# WWV_Radio_V1_11.net
KiCad netlist of a schematic drawn in EAGLE
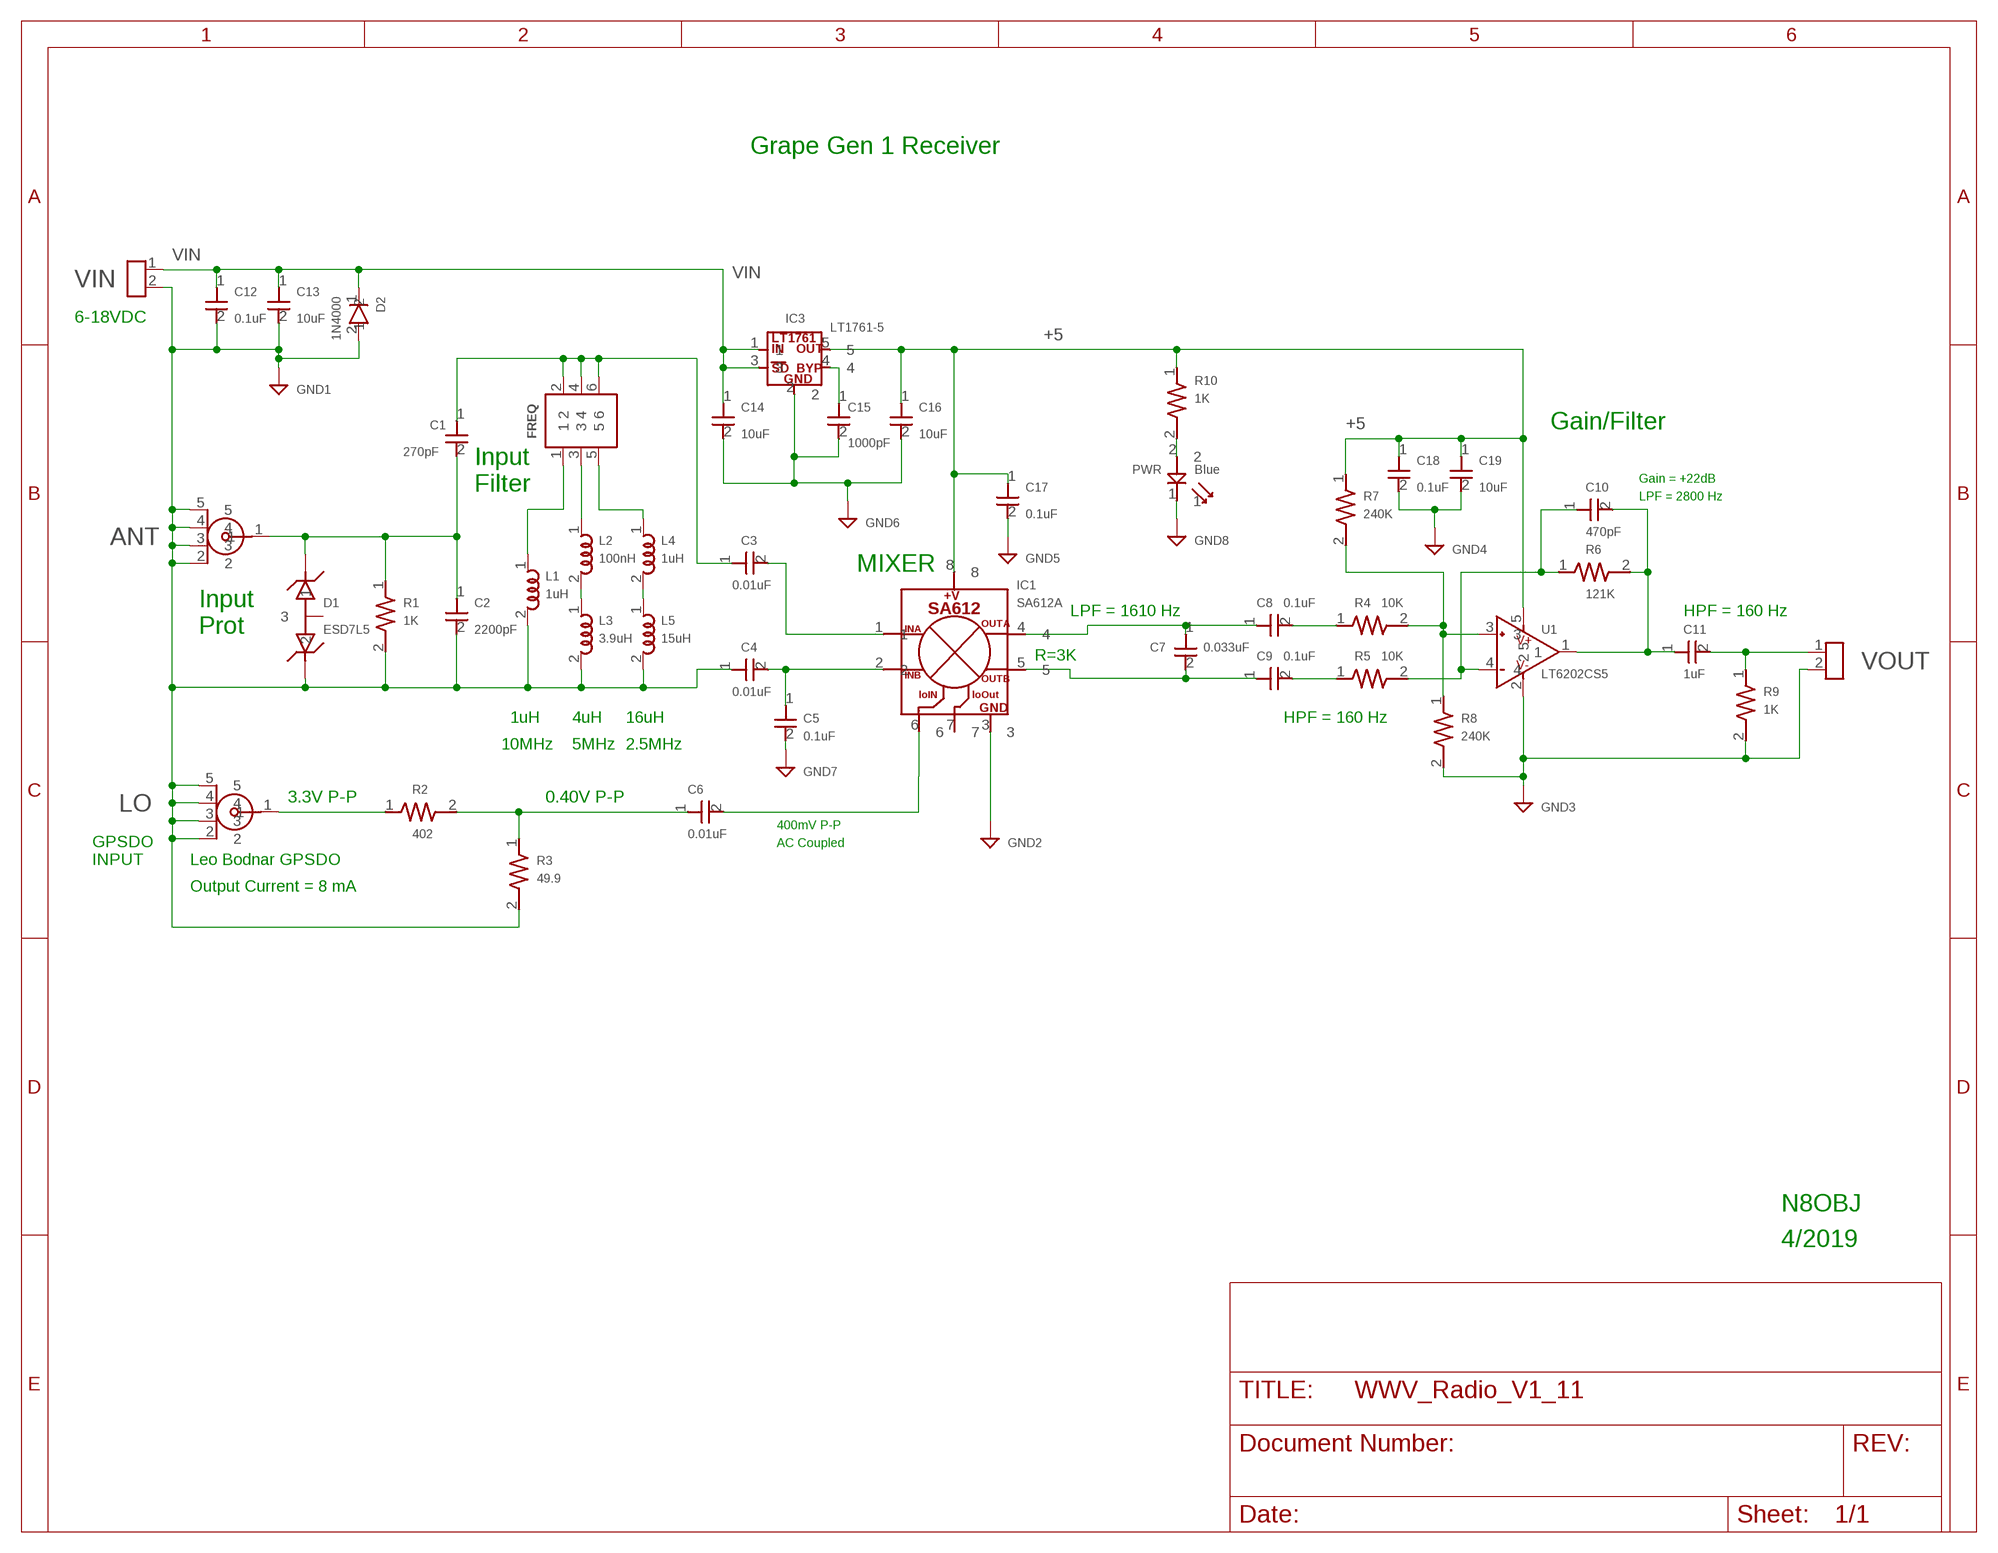
[diagram p0: schematic, sheet 1]

(export (version "E")
  (design (tool "Eeschema 10.0.6"))
  (components
    (comp (ref "ANT")
      (value "SMAEDGEPCB")
      (footprint "eagle-import:SMAEDGEPCB")
      (libsource (lib "eagle-import") (part "SMAEDGEPCB"))
    )
    (comp (ref "C1")
      (value "270pF")
      (footprint "eagle-import:C0805")
      (libsource (lib "eagle-import") (part "C0805"))
    )
    (comp (ref "C2")
      (value "2200pF")
      (footprint "eagle-import:C0805")
      (libsource (lib "eagle-import") (part "C0805"))
    )
    (comp (ref "C3")
      (value "0.01uF")
      (footprint "eagle-import:C0805")
      (libsource (lib "eagle-import") (part "C0805"))
    )
    (comp (ref "C4")
      (value "0.01uF")
      (footprint "eagle-import:C0805")
      (libsource (lib "eagle-import") (part "C0805"))
    )
    (comp (ref "C5")
      (value "0.1uF")
      (footprint "eagle-import:C0805")
      (libsource (lib "eagle-import") (part "C0805"))
    )
    (comp (ref "C6")
      (value "0.01uF")
      (footprint "eagle-import:C0805")
      (libsource (lib "eagle-import") (part "C0805"))
    )
    (comp (ref "C7")
      (value "0.033uF")
      (footprint "eagle-import:C0805")
      (libsource (lib "eagle-import") (part "C0805"))
    )
    (comp (ref "C8")
      (value "0.1uF")
      (footprint "eagle-import:C0805")
      (libsource (lib "eagle-import") (part "C0805"))
    )
    (comp (ref "C9")
      (value "0.1uF")
      (footprint "eagle-import:C0805")
      (libsource (lib "eagle-import") (part "C0805"))
    )
    (comp (ref "C10")
      (value "470pF")
      (footprint "eagle-import:C0805")
      (libsource (lib "eagle-import") (part "C0805"))
    )
    (comp (ref "C11")
      (value "1uF")
      (footprint "eagle-import:C0805")
      (libsource (lib "eagle-import") (part "C0805"))
    )
    (comp (ref "C12")
      (value "0.1uF")
      (footprint "eagle-import:C0805")
      (libsource (lib "eagle-import") (part "C0805"))
    )
    (comp (ref "C13")
      (value "10uF")
      (footprint "eagle-import:C0805")
      (libsource (lib "eagle-import") (part "C0805"))
    )
    (comp (ref "C14")
      (value "10uF")
      (footprint "eagle-import:C0805")
      (libsource (lib "eagle-import") (part "C0805"))
    )
    (comp (ref "C15")
      (value "1000pF")
      (footprint "eagle-import:C0805")
      (libsource (lib "eagle-import") (part "C0805"))
    )
    (comp (ref "C16")
      (value "10uF")
      (footprint "eagle-import:C0805")
      (libsource (lib "eagle-import") (part "C0805"))
    )
    (comp (ref "C17")
      (value "0.1uF")
      (footprint "eagle-import:C0805")
      (libsource (lib "eagle-import") (part "C0805"))
    )
    (comp (ref "C18")
      (value "0.1uF")
      (footprint "eagle-import:C0805")
      (libsource (lib "eagle-import") (part "C0805"))
    )
    (comp (ref "C19")
      (value "10uF")
      (footprint "eagle-import:C0805")
      (libsource (lib "eagle-import") (part "C0805"))
    )
    (comp (ref "D1")
      (value "ESD7L5")
      (footprint "eagle-import:ESD7L")
      (libsource (lib "eagle-import") (part "ESD7L"))
    )
    (comp (ref "D2")
      (value "1N4000")
      (footprint "eagle-import:1N4000_PTH")
      (libsource (lib "eagle-import") (part "1N4000_PTH"))
    )
    (comp (ref "FREQ")
      (value "2X3PINHEADER")
      (footprint "eagle-import:2X3PINHEADER")
      (libsource (lib "eagle-import") (part "2X3PINHEADER"))
    )
    (comp (ref "IC1")
      (value "SA612A")
      (footprint "eagle-import:SO08")
      (libsource (lib "eagle-import") (part "SA612A"))
    )
    (comp (ref "IC3")
      (value "LT1761-5")
      (footprint "eagle-import:TSOT-23")
      (libsource (lib "eagle-import") (part "LT1761-X"))
    )
    (comp (ref "L1")
      (value "1uH")
      (footprint "eagle-import:R1206")
      (libsource (lib "eagle-import") (part "L1206"))
    )
    (comp (ref "L2")
      (value "100nH")
      (footprint "eagle-import:R1206")
      (libsource (lib "eagle-import") (part "L1206"))
    )
    (comp (ref "L3")
      (value "3.9uH")
      (footprint "eagle-import:R1206")
      (libsource (lib "eagle-import") (part "L1206"))
    )
    (comp (ref "L4")
      (value "1uH")
      (footprint "eagle-import:R1206")
      (libsource (lib "eagle-import") (part "L1206"))
    )
    (comp (ref "L5")
      (value "15uH")
      (footprint "eagle-import:R1206")
      (libsource (lib "eagle-import") (part "L1206"))
    )
    (comp (ref "LO")
      (value "SMAEDGEPCB")
      (footprint "eagle-import:SMAEDGEPCB")
      (libsource (lib "eagle-import") (part "SMAEDGEPCB"))
    )
    (comp (ref "PWR")
      (value "Blue")
      (footprint "eagle-import:LED0805")
      (libsource (lib "eagle-import") (part "LED0805"))
    )
    (comp (ref "R1")
      (value "1K")
      (footprint "eagle-import:R0805")
      (libsource (lib "eagle-import") (part "R0805"))
    )
    (comp (ref "R2")
      (value "402")
      (footprint "eagle-import:R0805")
      (libsource (lib "eagle-import") (part "R0805"))
    )
    (comp (ref "R3")
      (value "49.9")
      (footprint "eagle-import:R0805")
      (libsource (lib "eagle-import") (part "R0805"))
    )
    (comp (ref "R4")
      (value "10K")
      (footprint "eagle-import:R0805")
      (libsource (lib "eagle-import") (part "R0805"))
    )
    (comp (ref "R5")
      (value "10K")
      (footprint "eagle-import:R0805")
      (libsource (lib "eagle-import") (part "R0805"))
    )
    (comp (ref "R6")
      (value "121K")
      (footprint "eagle-import:R0805")
      (libsource (lib "eagle-import") (part "R0805"))
    )
    (comp (ref "R7")
      (value "240K")
      (footprint "eagle-import:R0805")
      (libsource (lib "eagle-import") (part "R0805"))
    )
    (comp (ref "R8")
      (value "240K")
      (footprint "eagle-import:R0805")
      (libsource (lib "eagle-import") (part "R0805"))
    )
    (comp (ref "R9")
      (value "1K")
      (footprint "eagle-import:R0805")
      (libsource (lib "eagle-import") (part "R0805"))
    )
    (comp (ref "R10")
      (value "1K")
      (footprint "eagle-import:R0805")
      (libsource (lib "eagle-import") (part "R0805"))
    )
    (comp (ref "U1")
      (value "LT6202CS5")
      (footprint "eagle-import:SOT23_5")
      (libsource (lib "eagle-import") (part "LT6202CS5"))
    )
    (comp (ref "VIN")
      (value "2PINBERG")
      (footprint "eagle-import:2PINBERG")
      (libsource (lib "eagle-import") (part "2PINBERG"))
    )
    (comp (ref "VOUT")
      (value "2PINBERG")
      (footprint "eagle-import:2PINBERG")
      (libsource (lib "eagle-import") (part "2PINBERG"))
    )
  )
  (nets
    (net (code "1") (name "/+5") (class "Default")
      (node (ref "C16") (pin "1") (pinfunction "1_1") (pintype "bidirectional"))
      (node (ref "C17") (pin "1") (pinfunction "1_1") (pintype "bidirectional"))
      (node (ref "C18") (pin "1") (pinfunction "1_1") (pintype "bidirectional"))
      (node (ref "C19") (pin "1") (pinfunction "1_1") (pintype "bidirectional"))
      (node (ref "IC1") (pin "8") (pinfunction "8_8") (pintype "bidirectional"))
      (node (ref "IC3") (pin "5") (pinfunction "5_5") (pintype "bidirectional"))
      (node (ref "R10") (pin "1") (pinfunction "1_1") (pintype "bidirectional"))
      (node (ref "R7") (pin "1") (pinfunction "1_1") (pintype "bidirectional"))
      (node (ref "U1") (pin "5") (pinfunction "5_5") (pintype "bidirectional"))
    )
    (net (code "2") (name "/VIN") (class "Default")
      (node (ref "C12") (pin "1") (pinfunction "1_1") (pintype "bidirectional"))
      (node (ref "C13") (pin "1") (pinfunction "1_1") (pintype "bidirectional"))
      (node (ref "C14") (pin "1") (pinfunction "1_1") (pintype "bidirectional"))
      (node (ref "D2") (pin "1") (pinfunction "1_1") (pintype "bidirectional"))
      (node (ref "IC3") (pin "1") (pinfunction "1_1") (pintype "bidirectional"))
      (node (ref "IC3") (pin "3") (pinfunction "3_3") (pintype "bidirectional"))
      (node (ref "VIN") (pin "1") (pinfunction "1_1") (pintype "bidirectional"))
    )
    (net (code "3") (name "GND") (class "Default")
      (node (ref "ANT") (pin "2") (pinfunction "2_2") (pintype "bidirectional"))
      (node (ref "ANT") (pin "3") (pinfunction "3_3") (pintype "bidirectional"))
      (node (ref "ANT") (pin "4") (pinfunction "4_4") (pintype "bidirectional"))
      (node (ref "ANT") (pin "5") (pinfunction "5_5") (pintype "bidirectional"))
      (node (ref "C12") (pin "2") (pinfunction "2_2") (pintype "bidirectional"))
      (node (ref "C13") (pin "2") (pinfunction "2_2") (pintype "bidirectional"))
      (node (ref "C14") (pin "2") (pinfunction "2_2") (pintype "bidirectional"))
      (node (ref "C15") (pin "2") (pinfunction "2_2") (pintype "bidirectional"))
      (node (ref "C16") (pin "2") (pinfunction "2_2") (pintype "bidirectional"))
      (node (ref "C17") (pin "2") (pinfunction "2_2") (pintype "bidirectional"))
      (node (ref "C18") (pin "2") (pinfunction "2_2") (pintype "bidirectional"))
      (node (ref "C19") (pin "2") (pinfunction "2_2") (pintype "bidirectional"))
      (node (ref "C2") (pin "2") (pinfunction "2_2") (pintype "bidirectional"))
      (node (ref "C4") (pin "1") (pinfunction "1_1") (pintype "bidirectional"))
      (node (ref "C5") (pin "2") (pinfunction "2_2") (pintype "bidirectional"))
      (node (ref "D1") (pin "2") (pinfunction "2_2") (pintype "bidirectional"))
      (node (ref "D2") (pin "2") (pinfunction "2_2") (pintype "bidirectional"))
      (node (ref "IC1") (pin "3") (pinfunction "3_3") (pintype "bidirectional"))
      (node (ref "IC3") (pin "2") (pinfunction "2_2") (pintype "bidirectional"))
      (node (ref "L1") (pin "2") (pinfunction "2_2") (pintype "bidirectional"))
      (node (ref "L3") (pin "2") (pinfunction "2_2") (pintype "bidirectional"))
      (node (ref "L5") (pin "2") (pinfunction "2_2") (pintype "bidirectional"))
      (node (ref "LO") (pin "2") (pinfunction "2_2") (pintype "bidirectional"))
      (node (ref "LO") (pin "3") (pinfunction "3_3") (pintype "bidirectional"))
      (node (ref "LO") (pin "4") (pinfunction "4_4") (pintype "bidirectional"))
      (node (ref "LO") (pin "5") (pinfunction "5_5") (pintype "bidirectional"))
      (node (ref "PWR") (pin "1") (pinfunction "1_1") (pintype "bidirectional"))
      (node (ref "R1") (pin "2") (pinfunction "2_2") (pintype "bidirectional"))
      (node (ref "R3") (pin "2") (pinfunction "2_2") (pintype "bidirectional"))
      (node (ref "R8") (pin "2") (pinfunction "2_2") (pintype "bidirectional"))
      (node (ref "R9") (pin "2") (pinfunction "2_2") (pintype "bidirectional"))
      (node (ref "U1") (pin "2") (pinfunction "2_2") (pintype "bidirectional"))
      (node (ref "VIN") (pin "2") (pinfunction "2_2") (pintype "bidirectional"))
      (node (ref "VOUT") (pin "2") (pinfunction "2_2") (pintype "bidirectional"))
    )
    (net (code "4") (name "Net-(ANT-Pad1)") (class "Default")
      (node (ref "ANT") (pin "1") (pinfunction "1_1") (pintype "bidirectional"))
      (node (ref "C1") (pin "2") (pinfunction "2_2") (pintype "bidirectional"))
      (node (ref "C2") (pin "1") (pinfunction "1_1") (pintype "bidirectional"))
      (node (ref "D1") (pin "1") (pinfunction "1_1") (pintype "bidirectional"))
      (node (ref "R1") (pin "1") (pinfunction "1_1") (pintype "bidirectional"))
    )
    (net (code "5") (name "Net-(C1-Pad1)") (class "Default")
      (node (ref "C1") (pin "1") (pinfunction "1_1") (pintype "bidirectional"))
      (node (ref "C3") (pin "1") (pinfunction "1_1") (pintype "bidirectional"))
      (node (ref "FREQ") (pin "2") (pinfunction "2_2") (pintype "bidirectional"))
      (node (ref "FREQ") (pin "4") (pinfunction "4_4") (pintype "bidirectional"))
      (node (ref "FREQ") (pin "6") (pinfunction "6_6") (pintype "bidirectional"))
    )
    (net (code "6") (name "Net-(C3-Pad2)") (class "Default")
      (node (ref "C3") (pin "2") (pinfunction "2_2") (pintype "bidirectional"))
      (node (ref "IC1") (pin "1") (pinfunction "1_1") (pintype "bidirectional"))
    )
    (net (code "7") (name "Net-(C4-Pad2)") (class "Default")
      (node (ref "C4") (pin "2") (pinfunction "2_2") (pintype "bidirectional"))
      (node (ref "C5") (pin "1") (pinfunction "1_1") (pintype "bidirectional"))
      (node (ref "IC1") (pin "2") (pinfunction "2_2") (pintype "bidirectional"))
    )
    (net (code "8") (name "Net-(C6-Pad1)") (class "Default")
      (node (ref "C6") (pin "1") (pinfunction "1_1") (pintype "bidirectional"))
      (node (ref "R2") (pin "2") (pinfunction "2_2") (pintype "bidirectional"))
      (node (ref "R3") (pin "1") (pinfunction "1_1") (pintype "bidirectional"))
    )
    (net (code "9") (name "Net-(C6-Pad2)") (class "Default")
      (node (ref "C6") (pin "2") (pinfunction "2_2") (pintype "bidirectional"))
      (node (ref "IC1") (pin "6") (pinfunction "6_6") (pintype "bidirectional"))
    )
    (net (code "10") (name "Net-(C7-Pad1)") (class "Default")
      (node (ref "C7") (pin "1") (pinfunction "1_1") (pintype "bidirectional"))
      (node (ref "C8") (pin "1") (pinfunction "1_1") (pintype "bidirectional"))
      (node (ref "IC1") (pin "4") (pinfunction "4_4") (pintype "bidirectional"))
    )
    (net (code "11") (name "Net-(C7-Pad2)") (class "Default")
      (node (ref "C7") (pin "2") (pinfunction "2_2") (pintype "bidirectional"))
      (node (ref "C9") (pin "1") (pinfunction "1_1") (pintype "bidirectional"))
      (node (ref "IC1") (pin "5") (pinfunction "5_5") (pintype "bidirectional"))
    )
    (net (code "12") (name "Net-(C8-Pad2)") (class "Default")
      (node (ref "C8") (pin "2") (pinfunction "2_2") (pintype "bidirectional"))
      (node (ref "R4") (pin "1") (pinfunction "1_1") (pintype "bidirectional"))
    )
    (net (code "13") (name "Net-(C9-Pad2)") (class "Default")
      (node (ref "C9") (pin "2") (pinfunction "2_2") (pintype "bidirectional"))
      (node (ref "R5") (pin "1") (pinfunction "1_1") (pintype "bidirectional"))
    )
    (net (code "14") (name "Net-(C10-Pad1)") (class "Default")
      (node (ref "C10") (pin "1") (pinfunction "1_1") (pintype "bidirectional"))
      (node (ref "R5") (pin "2") (pinfunction "2_2") (pintype "bidirectional"))
      (node (ref "R6") (pin "1") (pinfunction "1_1") (pintype "bidirectional"))
      (node (ref "U1") (pin "4") (pinfunction "4_4") (pintype "bidirectional"))
    )
    (net (code "15") (name "Net-(C10-Pad2)") (class "Default")
      (node (ref "C10") (pin "2") (pinfunction "2_2") (pintype "bidirectional"))
      (node (ref "C11") (pin "1") (pinfunction "1_1") (pintype "bidirectional"))
      (node (ref "R6") (pin "2") (pinfunction "2_2") (pintype "bidirectional"))
      (node (ref "U1") (pin "1") (pinfunction "1_1") (pintype "bidirectional"))
    )
    (net (code "16") (name "Net-(C11-Pad2)") (class "Default")
      (node (ref "C11") (pin "2") (pinfunction "2_2") (pintype "bidirectional"))
      (node (ref "R9") (pin "1") (pinfunction "1_1") (pintype "bidirectional"))
      (node (ref "VOUT") (pin "1") (pinfunction "1_1") (pintype "bidirectional"))
    )
    (net (code "17") (name "Net-(C15-Pad1)") (class "Default")
      (node (ref "C15") (pin "1") (pinfunction "1_1") (pintype "bidirectional"))
      (node (ref "IC3") (pin "4") (pinfunction "4_4") (pintype "bidirectional"))
    )
    (net (code "18") (name "Net-(FREQ-Pad1)") (class "Default")
      (node (ref "FREQ") (pin "1") (pinfunction "1_1") (pintype "bidirectional"))
      (node (ref "L1") (pin "1") (pinfunction "1_1") (pintype "bidirectional"))
    )
    (net (code "19") (name "Net-(FREQ-Pad3)") (class "Default")
      (node (ref "FREQ") (pin "3") (pinfunction "3_3") (pintype "bidirectional"))
      (node (ref "L2") (pin "1") (pinfunction "1_1") (pintype "bidirectional"))
    )
    (net (code "20") (name "Net-(FREQ-Pad5)") (class "Default")
      (node (ref "FREQ") (pin "5") (pinfunction "5_5") (pintype "bidirectional"))
      (node (ref "L4") (pin "1") (pinfunction "1_1") (pintype "bidirectional"))
    )
    (net (code "21") (name "Net-(L2-Pad2)") (class "Default")
      (node (ref "L2") (pin "2") (pinfunction "2_2") (pintype "bidirectional"))
      (node (ref "L3") (pin "1") (pinfunction "1_1") (pintype "bidirectional"))
    )
    (net (code "22") (name "Net-(L4-Pad2)") (class "Default")
      (node (ref "L4") (pin "2") (pinfunction "2_2") (pintype "bidirectional"))
      (node (ref "L5") (pin "1") (pinfunction "1_1") (pintype "bidirectional"))
    )
    (net (code "23") (name "Net-(LO-Pad1)") (class "Default")
      (node (ref "LO") (pin "1") (pinfunction "1_1") (pintype "bidirectional"))
      (node (ref "R2") (pin "1") (pinfunction "1_1") (pintype "bidirectional"))
    )
    (net (code "24") (name "Net-(PWR-Pad2)") (class "Default")
      (node (ref "PWR") (pin "2") (pinfunction "2_2") (pintype "bidirectional"))
      (node (ref "R10") (pin "2") (pinfunction "2_2") (pintype "bidirectional"))
    )
    (net (code "25") (name "Net-(R4-Pad2)") (class "Default")
      (node (ref "R4") (pin "2") (pinfunction "2_2") (pintype "bidirectional"))
      (node (ref "R7") (pin "2") (pinfunction "2_2") (pintype "bidirectional"))
      (node (ref "R8") (pin "1") (pinfunction "1_1") (pintype "bidirectional"))
      (node (ref "U1") (pin "3") (pinfunction "3_3") (pintype "bidirectional"))
    )
    (net (code "26") (name "unconnected-(D1-Pad3)") (class "Default")
      (node (ref "D1") (pin "3") (pinfunction "3_3") (pintype "bidirectional"))
    )
    (net (code "27") (name "unconnected-(IC1-Pad7)") (class "Default")
      (node (ref "IC1") (pin "7") (pinfunction "7_7") (pintype "bidirectional"))
    )
  )
)
